# psg-8ch.net
KiCad netlist of a schematic drawn in EAGLE
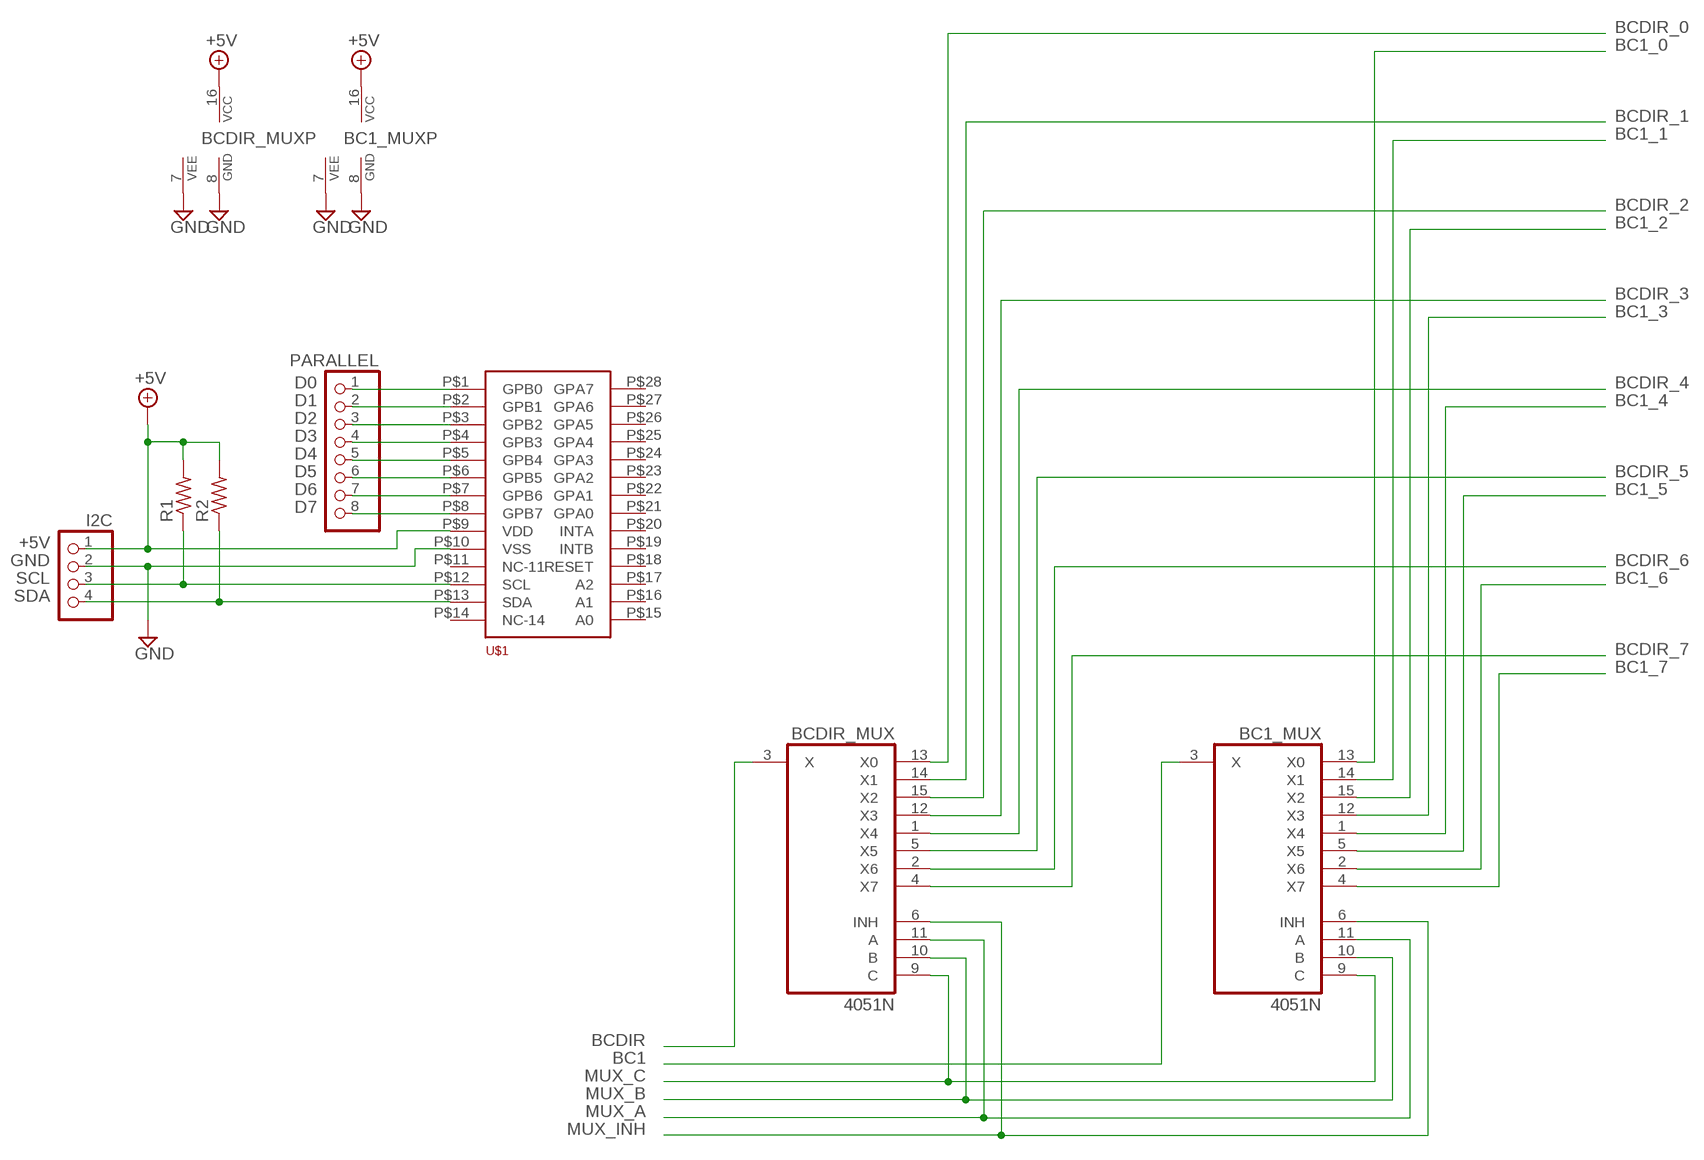
[diagram p0: schematic, sheet 1]

(export (version "E")
  (design (tool "Eeschema 10.0.6"))
  (components
    (comp (ref "BC1_MUX")
      (value "4051N")
      (footprint "eagle-import:DIL16")
      (libsource (lib "eagle-import") (part "4051N"))
    )
    (comp (ref "BCDIR_MUX")
      (value "4051N")
      (footprint "eagle-import:DIL16")
      (libsource (lib "eagle-import") (part "4051N"))
    )
    (comp (ref "I2C")
      (value "PINHD-1X4")
      (footprint "eagle-import:1X04")
      (libsource (lib "eagle-import") (part "PINHD-1X4"))
    )
    (comp (ref "PARALLEL")
      (value "PINHD-1X8")
      (footprint "eagle-import:1X08")
      (libsource (lib "eagle-import") (part "PINHD-1X8"))
    )
    (comp (ref "R1")
      (value "6MM.3")
      (footprint "eagle-import:R0207_3")
      (libsource (lib "eagle-import") (part "6MM.3"))
    )
    (comp (ref "R2")
      (value "6MM.3")
      (footprint "eagle-import:R0207_3")
      (libsource (lib "eagle-import") (part "6MM.3"))
    )
    (comp (ref "U$1")
      (value "MCP23017-E/SP")
      (footprint "eagle-import:DIP28")
      (libsource (lib "eagle-import") (part "MCP23017-E/SP"))
    )
  )
  (nets
    (net (code "1") (name "+5V") (class "Default")
      (node (ref "BC1_MUX") (pin "16") (pinfunction "VCC_16") (pintype "power_in"))
      (node (ref "BCDIR_MUX") (pin "16") (pinfunction "VCC_16") (pintype "power_in"))
      (node (ref "I2C") (pin "1") (pinfunction "1_1") (pintype "passive"))
      (node (ref "R1") (pin "2") (pinfunction "2_2") (pintype "passive"))
      (node (ref "R2") (pin "2") (pinfunction "2_2") (pintype "passive"))
      (node (ref "U$1") (pin "P$9") (pinfunction "VDD_P$9") (pintype "bidirectional"))
    )
    (net (code "2") (name "/BC1") (class "Default")
      (node (ref "BC1_MUX") (pin "3") (pinfunction "X_3") (pintype "bidirectional"))
    )
    (net (code "3") (name "/BC1_0") (class "Default")
      (node (ref "BC1_MUX") (pin "13") (pinfunction "X0_13") (pintype "bidirectional"))
    )
    (net (code "4") (name "/BC1_1") (class "Default")
      (node (ref "BC1_MUX") (pin "14") (pinfunction "X1_14") (pintype "bidirectional"))
    )
    (net (code "5") (name "/BC1_2") (class "Default")
      (node (ref "BC1_MUX") (pin "15") (pinfunction "X2_15") (pintype "bidirectional"))
    )
    (net (code "6") (name "/BC1_3") (class "Default")
      (node (ref "BC1_MUX") (pin "12") (pinfunction "X3_12") (pintype "bidirectional"))
    )
    (net (code "7") (name "/BC1_4") (class "Default")
      (node (ref "BC1_MUX") (pin "1") (pinfunction "X4_1") (pintype "bidirectional"))
    )
    (net (code "8") (name "/BC1_5") (class "Default")
      (node (ref "BC1_MUX") (pin "5") (pinfunction "X5_5") (pintype "bidirectional"))
    )
    (net (code "9") (name "/BC1_6") (class "Default")
      (node (ref "BC1_MUX") (pin "2") (pinfunction "X6_2") (pintype "bidirectional"))
    )
    (net (code "10") (name "/BC1_7") (class "Default")
      (node (ref "BC1_MUX") (pin "4") (pinfunction "X7_4") (pintype "bidirectional"))
    )
    (net (code "11") (name "/BCDIR") (class "Default")
      (node (ref "BCDIR_MUX") (pin "3") (pinfunction "X_3") (pintype "bidirectional"))
    )
    (net (code "12") (name "/BCDIR_0") (class "Default")
      (node (ref "BCDIR_MUX") (pin "13") (pinfunction "X0_13") (pintype "bidirectional"))
    )
    (net (code "13") (name "/BCDIR_1") (class "Default")
      (node (ref "BCDIR_MUX") (pin "14") (pinfunction "X1_14") (pintype "bidirectional"))
    )
    (net (code "14") (name "/BCDIR_2") (class "Default")
      (node (ref "BCDIR_MUX") (pin "15") (pinfunction "X2_15") (pintype "bidirectional"))
    )
    (net (code "15") (name "/BCDIR_3") (class "Default")
      (node (ref "BCDIR_MUX") (pin "12") (pinfunction "X3_12") (pintype "bidirectional"))
    )
    (net (code "16") (name "/BCDIR_4") (class "Default")
      (node (ref "BCDIR_MUX") (pin "1") (pinfunction "X4_1") (pintype "bidirectional"))
    )
    (net (code "17") (name "/BCDIR_5") (class "Default")
      (node (ref "BCDIR_MUX") (pin "5") (pinfunction "X5_5") (pintype "bidirectional"))
    )
    (net (code "18") (name "/BCDIR_6") (class "Default")
      (node (ref "BCDIR_MUX") (pin "2") (pinfunction "X6_2") (pintype "bidirectional"))
    )
    (net (code "19") (name "/BCDIR_7") (class "Default")
      (node (ref "BCDIR_MUX") (pin "4") (pinfunction "X7_4") (pintype "bidirectional"))
    )
    (net (code "20") (name "/D0") (class "Default")
      (node (ref "PARALLEL") (pin "1") (pinfunction "1_1") (pintype "passive"))
      (node (ref "U$1") (pin "P$1") (pinfunction "GPB0_P$1") (pintype "bidirectional"))
    )
    (net (code "21") (name "/D1") (class "Default")
      (node (ref "PARALLEL") (pin "2") (pinfunction "2_2") (pintype "passive"))
      (node (ref "U$1") (pin "P$2") (pinfunction "GPB1_P$2") (pintype "bidirectional"))
    )
    (net (code "22") (name "/D2") (class "Default")
      (node (ref "PARALLEL") (pin "3") (pinfunction "3_3") (pintype "passive"))
      (node (ref "U$1") (pin "P$3") (pinfunction "GPB2_P$3") (pintype "bidirectional"))
    )
    (net (code "23") (name "/D3") (class "Default")
      (node (ref "PARALLEL") (pin "4") (pinfunction "4_4") (pintype "passive"))
      (node (ref "U$1") (pin "P$4") (pinfunction "GPB3_P$4") (pintype "bidirectional"))
    )
    (net (code "24") (name "/D4") (class "Default")
      (node (ref "PARALLEL") (pin "5") (pinfunction "5_5") (pintype "passive"))
      (node (ref "U$1") (pin "P$5") (pinfunction "GPB4_P$5") (pintype "bidirectional"))
    )
    (net (code "25") (name "/D5") (class "Default")
      (node (ref "PARALLEL") (pin "6") (pinfunction "6_6") (pintype "passive"))
      (node (ref "U$1") (pin "P$6") (pinfunction "GPB5_P$6") (pintype "bidirectional"))
    )
    (net (code "26") (name "/D6") (class "Default")
      (node (ref "PARALLEL") (pin "7") (pinfunction "7_7") (pintype "passive"))
      (node (ref "U$1") (pin "P$7") (pinfunction "GPB6_P$7") (pintype "bidirectional"))
    )
    (net (code "27") (name "/D7") (class "Default")
      (node (ref "PARALLEL") (pin "8") (pinfunction "8_8") (pintype "passive"))
      (node (ref "U$1") (pin "P$8") (pinfunction "GPB7_P$8") (pintype "bidirectional"))
    )
    (net (code "28") (name "/MUX_A") (class "Default")
      (node (ref "BC1_MUX") (pin "11") (pinfunction "A_11") (pintype "input"))
      (node (ref "BCDIR_MUX") (pin "11") (pinfunction "A_11") (pintype "input"))
    )
    (net (code "29") (name "/MUX_B") (class "Default")
      (node (ref "BC1_MUX") (pin "10") (pinfunction "B_10") (pintype "input"))
      (node (ref "BCDIR_MUX") (pin "10") (pinfunction "B_10") (pintype "input"))
    )
    (net (code "30") (name "/MUX_C") (class "Default")
      (node (ref "BC1_MUX") (pin "9") (pinfunction "C_9") (pintype "input"))
      (node (ref "BCDIR_MUX") (pin "9") (pinfunction "C_9") (pintype "input"))
    )
    (net (code "31") (name "/MUX_INH") (class "Default")
      (node (ref "BC1_MUX") (pin "6") (pinfunction "INH_6") (pintype "input"))
      (node (ref "BCDIR_MUX") (pin "6") (pinfunction "INH_6") (pintype "input"))
    )
    (net (code "32") (name "/SCL") (class "Default")
      (node (ref "I2C") (pin "3") (pinfunction "3_3") (pintype "passive"))
      (node (ref "R1") (pin "1") (pinfunction "1_1") (pintype "passive"))
      (node (ref "U$1") (pin "P$12") (pinfunction "SCL_P$12") (pintype "bidirectional"))
    )
    (net (code "33") (name "/SDA") (class "Default")
      (node (ref "I2C") (pin "4") (pinfunction "4_4") (pintype "passive"))
      (node (ref "R2") (pin "1") (pinfunction "1_1") (pintype "passive"))
      (node (ref "U$1") (pin "P$13") (pinfunction "SDA_P$13") (pintype "bidirectional"))
    )
    (net (code "34") (name "GND") (class "Default")
      (node (ref "BC1_MUX") (pin "7") (pinfunction "VEE_7") (pintype "power_in"))
      (node (ref "BC1_MUX") (pin "8") (pinfunction "GND_8") (pintype "power_in"))
      (node (ref "BCDIR_MUX") (pin "7") (pinfunction "VEE_7") (pintype "power_in"))
      (node (ref "BCDIR_MUX") (pin "8") (pinfunction "GND_8") (pintype "power_in"))
      (node (ref "I2C") (pin "2") (pinfunction "2_2") (pintype "passive"))
      (node (ref "U$1") (pin "P$10") (pinfunction "VSS_P$10") (pintype "bidirectional"))
    )
    (net (code "35") (name "unconnected-(U$1-A0-PadP$15)") (class "Default")
      (node (ref "U$1") (pin "P$15") (pinfunction "A0_P$15") (pintype "bidirectional"))
    )
    (net (code "36") (name "unconnected-(U$1-A1-PadP$16)") (class "Default")
      (node (ref "U$1") (pin "P$16") (pinfunction "A1_P$16") (pintype "bidirectional"))
    )
    (net (code "37") (name "unconnected-(U$1-A2-PadP$17)") (class "Default")
      (node (ref "U$1") (pin "P$17") (pinfunction "A2_P$17") (pintype "bidirectional"))
    )
    (net (code "38") (name "unconnected-(U$1-GPA0-PadP$21)") (class "Default")
      (node (ref "U$1") (pin "P$21") (pinfunction "GPA0_P$21") (pintype "bidirectional"))
    )
    (net (code "39") (name "unconnected-(U$1-GPA1-PadP$22)") (class "Default")
      (node (ref "U$1") (pin "P$22") (pinfunction "GPA1_P$22") (pintype "bidirectional"))
    )
    (net (code "40") (name "unconnected-(U$1-GPA2-PadP$23)") (class "Default")
      (node (ref "U$1") (pin "P$23") (pinfunction "GPA2_P$23") (pintype "bidirectional"))
    )
    (net (code "41") (name "unconnected-(U$1-GPA3-PadP$24)") (class "Default")
      (node (ref "U$1") (pin "P$24") (pinfunction "GPA3_P$24") (pintype "bidirectional"))
    )
    (net (code "42") (name "unconnected-(U$1-GPA4-PadP$25)") (class "Default")
      (node (ref "U$1") (pin "P$25") (pinfunction "GPA4_P$25") (pintype "bidirectional"))
    )
    (net (code "43") (name "unconnected-(U$1-GPA5-PadP$26)") (class "Default")
      (node (ref "U$1") (pin "P$26") (pinfunction "GPA5_P$26") (pintype "bidirectional"))
    )
    (net (code "44") (name "unconnected-(U$1-GPA6-PadP$27)") (class "Default")
      (node (ref "U$1") (pin "P$27") (pinfunction "GPA6_P$27") (pintype "bidirectional"))
    )
    (net (code "45") (name "unconnected-(U$1-GPA7-PadP$28)") (class "Default")
      (node (ref "U$1") (pin "P$28") (pinfunction "GPA7_P$28") (pintype "bidirectional"))
    )
    (net (code "46") (name "unconnected-(U$1-INTA-PadP$20)") (class "Default")
      (node (ref "U$1") (pin "P$20") (pinfunction "INTA_P$20") (pintype "bidirectional"))
    )
    (net (code "47") (name "unconnected-(U$1-INTB-PadP$19)") (class "Default")
      (node (ref "U$1") (pin "P$19") (pinfunction "INTB_P$19") (pintype "bidirectional"))
    )
    (net (code "48") (name "unconnected-(U$1-NC-11-PadP$11)") (class "Default")
      (node (ref "U$1") (pin "P$11") (pinfunction "NC-11_P$11") (pintype "bidirectional"))
    )
    (net (code "49") (name "unconnected-(U$1-NC-14-PadP$14)") (class "Default")
      (node (ref "U$1") (pin "P$14") (pinfunction "NC-14_P$14") (pintype "bidirectional"))
    )
    (net (code "50") (name "unconnected-(U$1-RESET-PadP$18)") (class "Default")
      (node (ref "U$1") (pin "P$18") (pinfunction "RESET_P$18") (pintype "bidirectional"))
    )
  )
)
